# 20210523_EleksTube_IPS_extend_v1_1.net
KiCad netlist of a schematic drawn in Altium Designer
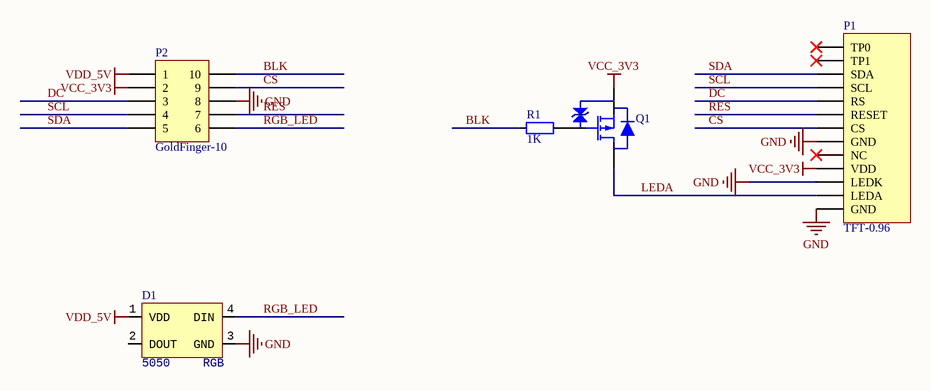
[diagram p0: 20210523_EleksTube_IPS_extend_v1_1.SchDoc]

(export (version "E")
  (design (tool "Eeschema 10.0.6"))
  (components
    (comp (ref "D1")
      (value "RGB")
      (footprint "LED_5050_WS2812B")
      (description "LED")
      (fields (field (name "TYPE") "5050"))
      (libsource (lib "KitSprout") (part "LED_5050_WS2812B"))
    )
    (comp (ref "P1")
      (value "TFT-0.96")
      (footprint "TFT-0.96")
      (description "Header, 13-Pin")
      (fields (field (name "PUBLISHER") "Altium Limited"))
      (libsource (lib "20210225_EleksTube_IPS_extend") (part "Header 13"))
    )
    (comp (ref "P2")
      (value "GoldFinger-10")
      (footprint "GoldFinger-10")
      (description "Header, 5-Pin, Dual row")
      (fields (field (name "PUBLISHER") "Altium Limited"))
      (libsource (lib "20210225_EleksTube_IPS_extend") (part "GoldFinger-10"))
    )
    (comp (ref "Q1")
      (value "AO3415A")
      (footprint "SOT23-3")
      (description "MOSFET")
      (fields (field (name "PUBLISHER") "Altium Limited"))
      (libsource (lib "MyPcbLib") (part "AO3415A"))
    )
    (comp (ref "R1")
      (value "1K")
      (footprint "RES_0402")
      (description "Resistor")
      (libsource (lib "MyPcbLib") (part "电阻-0402"))
    )
  )
  (nets
    (net (code "1") (name "/BLK") (class "Default")
      (node (ref "P2") (pin "10") (pinfunction "10_10") (pintype "passive"))
      (node (ref "R1") (pin "1") (pinfunction "1_1") (pintype "passive"))
    )
    (net (code "2") (name "/CS") (class "Default")
      (node (ref "P1") (pin "7") (pinfunction "CS_7") (pintype "passive"))
      (node (ref "P2") (pin "9") (pinfunction "9_9") (pintype "passive"))
    )
    (net (code "3") (name "/DC") (class "Default")
      (node (ref "P1") (pin "5") (pinfunction "RS_5") (pintype "passive"))
      (node (ref "P2") (pin "3") (pinfunction "3_3") (pintype "passive"))
    )
    (net (code "4") (name "/LEDA") (class "Default")
      (node (ref "P1") (pin "12") (pinfunction "LEDA_12") (pintype "passive"))
      (node (ref "Q1") (pin "3") (pinfunction "D_3") (pintype "passive"))
    )
    (net (code "5") (name "/RES") (class "Default")
      (node (ref "P1") (pin "6") (pinfunction "RESET_6") (pintype "passive"))
      (node (ref "P2") (pin "7") (pinfunction "7_7") (pintype "passive"))
    )
    (net (code "6") (name "/RGB_LED") (class "Default")
      (node (ref "D1") (pin "4") (pinfunction "DIN_4") (pintype "passive"))
      (node (ref "P2") (pin "6") (pinfunction "6_6") (pintype "passive"))
    )
    (net (code "7") (name "/SCL") (class "Default")
      (node (ref "P1") (pin "4") (pinfunction "SCL_4") (pintype "passive"))
      (node (ref "P2") (pin "4") (pinfunction "4_4") (pintype "passive"))
    )
    (net (code "8") (name "/SDA") (class "Default")
      (node (ref "P1") (pin "3") (pinfunction "SDA_3") (pintype "passive"))
      (node (ref "P2") (pin "5") (pinfunction "5_5") (pintype "passive"))
    )
    (net (code "9") (name "GND") (class "Default")
      (node (ref "D1") (pin "3") (pinfunction "GND_3") (pintype "passive"))
      (node (ref "P1") (pin "11") (pinfunction "LEDK_11") (pintype "passive"))
      (node (ref "P1") (pin "13") (pinfunction "GND_13") (pintype "passive"))
      (node (ref "P1") (pin "8") (pinfunction "GND_8") (pintype "passive"))
      (node (ref "P2") (pin "8") (pinfunction "8_8") (pintype "passive"))
    )
    (net (code "10") (name "Net-(Q1-G)") (class "Default")
      (node (ref "Q1") (pin "1") (pinfunction "G_1") (pintype "passive"))
      (node (ref "R1") (pin "2") (pinfunction "2_2") (pintype "passive"))
    )
    (net (code "11") (name "VCC_3V3") (class "Default")
      (node (ref "P1") (pin "10") (pinfunction "VDD_10") (pintype "passive"))
      (node (ref "P2") (pin "2") (pinfunction "2_2") (pintype "passive"))
      (node (ref "Q1") (pin "2") (pinfunction "S_2") (pintype "passive"))
    )
    (net (code "12") (name "VDD_5V") (class "Default")
      (node (ref "D1") (pin "1") (pinfunction "VDD_1") (pintype "passive"))
      (node (ref "P2") (pin "1") (pinfunction "1_1") (pintype "passive"))
    )
    (net (code "13") (name "unconnected-(D1-DOUT-Pad2)") (class "Default")
      (node (ref "D1") (pin "2") (pinfunction "DOUT_2") (pintype "passive"))
    )
    (net (code "14") (name "unconnected-(P1-NC-Pad9)") (class "Default")
      (node (ref "P1") (pin "9") (pinfunction "NC_9") (pintype "passive+no_connect"))
    )
    (net (code "15") (name "unconnected-(P1-TP0-Pad1)") (class "Default")
      (node (ref "P1") (pin "1") (pinfunction "TP0_1") (pintype "passive+no_connect"))
    )
    (net (code "16") (name "unconnected-(P1-TP1-Pad2)") (class "Default")
      (node (ref "P1") (pin "2") (pinfunction "TP1_2") (pintype "passive+no_connect"))
    )
  )
)
